# TSAL_Dummy.net
KiCad netlist of a schematic drawn in Altium Designer
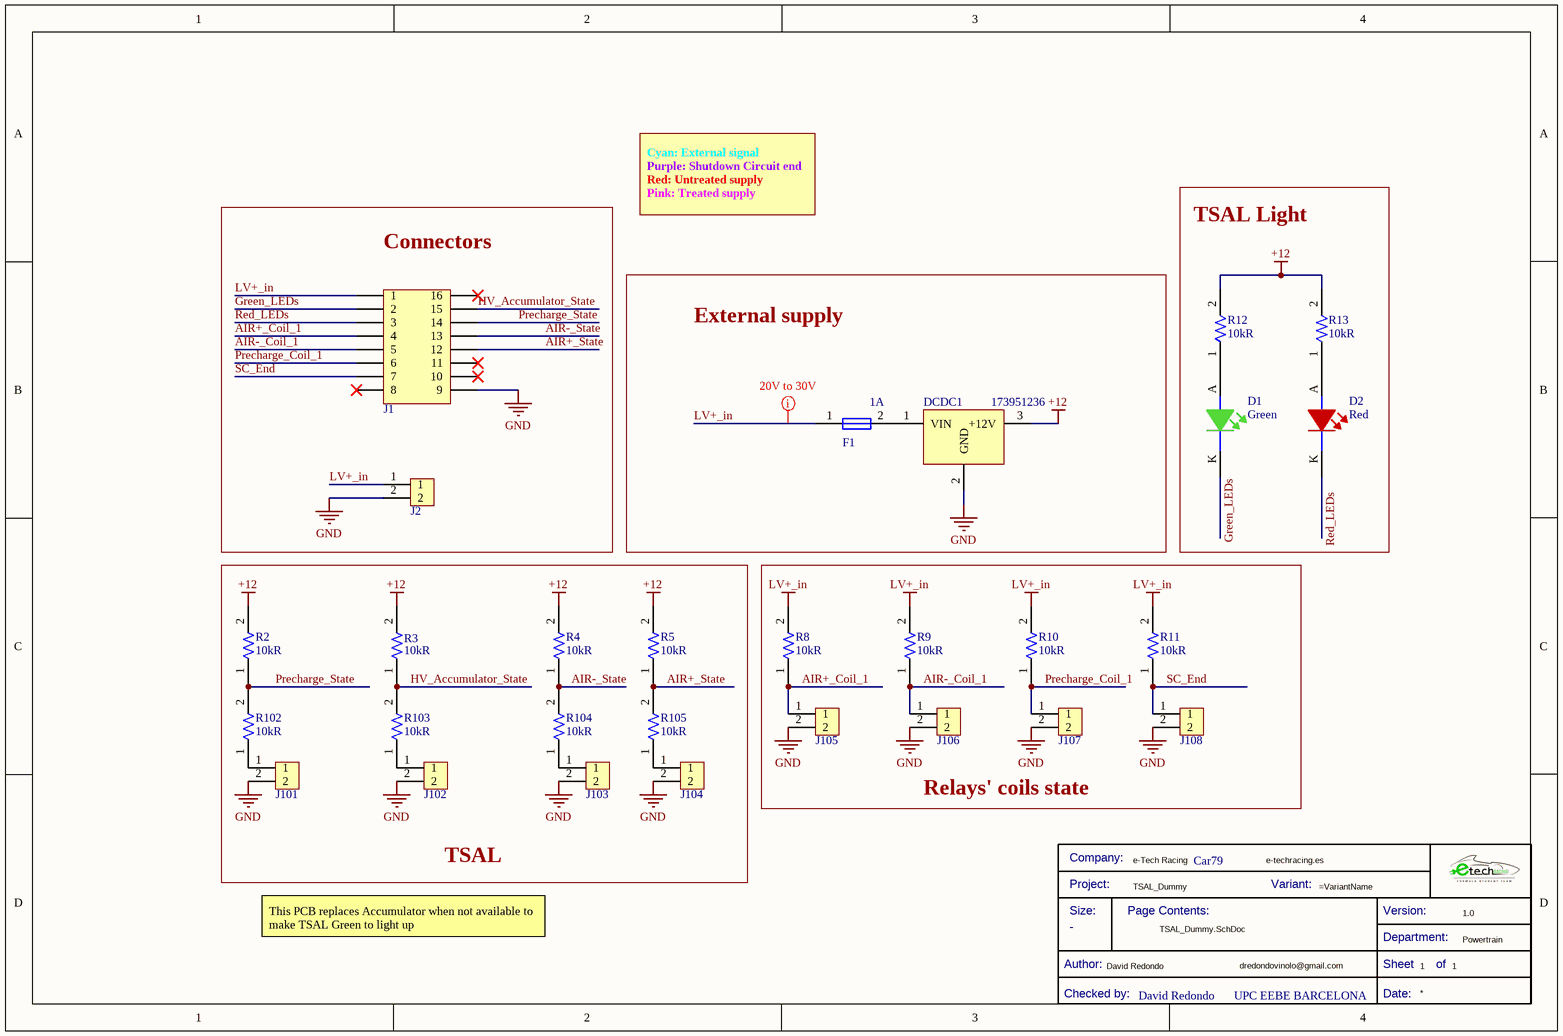
[diagram p0: TSAL_Dummy.SchDoc]

(export (version "E")
  (design (tool "Eeschema 10.0.6"))
  (components
    (comp (ref "*")
      (value "Title Block_template")
      (description "Standard Title Block")
      (fields
        (field (name "SIZE") "-")
        (field (name ".CREATOR") "GP")
        (field (name ".PCBCHECK") "GP")
        (field (name ".SCHCHECK") "GP")
      )
      (libsource (lib "e-Tech_Racing") (part "Title Block_template"))
    )
    (comp (ref "D1")
      (value "150080VS75000")
      (footprint "LED_0805_WE")
      (description "Led, Green, 570 Nm, 2 V, 30 Ma, 40 Mcd Rohs Compliant: Yes")
      (fields (field (name "COLOR") "Green") (field (name ".CREATOR") "DR"))
      (libsource (lib "Semiconductor") (part "LEDVS-0805-40"))
    )
    (comp (ref "D2")
      (value "150080RS75000")
      (footprint "LED_0805_WE")
      (description "0805(H=0.8mm) 红色 高亮 λD=625nm VF=2V IF=30mA PD=72mW")
      (fields (field (name "COLOR") "Red") (field (name ".CREATOR") "DR"))
      (libsource (lib "Semiconductor") (part "LEDRS-0805-150"))
    )
    (comp (ref "DCDC1")
      (value "173951236")
      (footprint "DCDC_Magi3c")
      (description "Fdsm Fixed Step Down Regulator M")
      (libsource (lib "Semiconductor") (part "DCDC-36V/12V-0.5A"))
    )
    (comp (ref "F1")
      (value "0437001.WRA")
      (footprint "Fuse_1206")
      (description "Fuse Chip Fast Acting 1A 63V SMD Solder Pad 1206 Ceramic T/R Automotive")
      (fields
        (field (name "MANUFACTURER") "Littelfuse")
        (field (name "CURRENT RATING") "1A")
        (field (name ".CREATOR") "DO")
      )
      (libsource (lib "Filter components") (part "Fuse_1A_63V_1206"))
    )
    (comp (ref "J1")
      (value "1053101116")
      (footprint "J_NanoFit_2x8_V")
      (fields (field (name ".CREATOR") "AC"))
      (libsource (lib "Electromechanical") (part "J_NanoFit_2x8_V"))
    )
    (comp (ref "J2")
      (value "436500215")
      (footprint "J_MicroFit_2x1")
      (description "Header 1 Row Vertical Polarizing Peg 2 Pin SMT/Glow Wire Compatible Tin Plate")
      (libsource (lib "Electromechanical") (part "J_MicroFit_2x1"))
    )
    (comp (ref "J101")
      (value "61300211121")
      (footprint "J_Pinheader_1x2")
      (description "CONN HEADER 2 POS 2.54")
      (fields (field (name "MANUFACTURER") "Molex") (field (name ".CREATOR") "GP"))
      (libsource (lib "Electromechanical") (part "J_Jumper"))
    )
    (comp (ref "J102")
      (value "61300211121")
      (footprint "J_Pinheader_1x2")
      (description "CONN HEADER 2 POS 2.54")
      (fields (field (name "MANUFACTURER") "Molex") (field (name ".CREATOR") "GP"))
      (libsource (lib "Electromechanical") (part "J_Jumper"))
    )
    (comp (ref "J103")
      (value "61300211121")
      (footprint "J_Pinheader_1x2")
      (description "CONN HEADER 2 POS 2.54")
      (fields (field (name "MANUFACTURER") "Molex") (field (name ".CREATOR") "GP"))
      (libsource (lib "Electromechanical") (part "J_Jumper"))
    )
    (comp (ref "J104")
      (value "61300211121")
      (footprint "J_Pinheader_1x2")
      (description "CONN HEADER 2 POS 2.54")
      (fields (field (name "MANUFACTURER") "Molex") (field (name ".CREATOR") "GP"))
      (libsource (lib "Electromechanical") (part "J_Jumper"))
    )
    (comp (ref "J105")
      (value "61300211121")
      (footprint "J_Pinheader_1x2")
      (description "CONN HEADER 2 POS 2.54")
      (fields (field (name "MANUFACTURER") "Molex") (field (name ".CREATOR") "GP"))
      (libsource (lib "Electromechanical") (part "J_Jumper"))
    )
    (comp (ref "J106")
      (value "61300211121")
      (footprint "J_Pinheader_1x2")
      (description "CONN HEADER 2 POS 2.54")
      (fields (field (name "MANUFACTURER") "Molex") (field (name ".CREATOR") "GP"))
      (libsource (lib "Electromechanical") (part "J_Jumper"))
    )
    (comp (ref "J107")
      (value "61300211121")
      (footprint "J_Pinheader_1x2")
      (description "CONN HEADER 2 POS 2.54")
      (fields (field (name "MANUFACTURER") "Molex") (field (name ".CREATOR") "GP"))
      (libsource (lib "Electromechanical") (part "J_Jumper"))
    )
    (comp (ref "J108")
      (value "61300211121")
      (footprint "J_Pinheader_1x2")
      (description "CONN HEADER 2 POS 2.54")
      (fields (field (name "MANUFACTURER") "Molex") (field (name ".CREATOR") "GP"))
      (libsource (lib "Electromechanical") (part "J_Jumper"))
    )
    (comp (ref "R2")
      (value "CR0805-JW-103ELF")
      (footprint "R0805FTK")
      (fields
        (field (name "TOLERANCE") "5%")
        (field (name "RESISTANCE") "10kR")
        (field (name ".CREATOR") "DR")
      )
      (libsource (lib "Passives") (part "R10k-0805FTK"))
    )
    (comp (ref "R3")
      (value "CR0805-JW-103ELF")
      (footprint "R0805FTK")
      (fields
        (field (name "TOLERANCE") "5%")
        (field (name "RESISTANCE") "10kR")
        (field (name ".CREATOR") "DR")
      )
      (libsource (lib "Passives") (part "R10k-0805FTK"))
    )
    (comp (ref "R4")
      (value "CR0805-JW-103ELF")
      (footprint "R0805FTK")
      (fields
        (field (name "TOLERANCE") "5%")
        (field (name "RESISTANCE") "10kR")
        (field (name ".CREATOR") "DR")
      )
      (libsource (lib "Passives") (part "R10k-0805FTK"))
    )
    (comp (ref "R5")
      (value "CR0805-JW-103ELF")
      (footprint "R0805FTK")
      (fields
        (field (name "TOLERANCE") "5%")
        (field (name "RESISTANCE") "10kR")
        (field (name ".CREATOR") "DR")
      )
      (libsource (lib "Passives") (part "R10k-0805FTK"))
    )
    (comp (ref "R8")
      (value "CR0805-JW-103ELF")
      (footprint "R0805FTK")
      (fields
        (field (name "TOLERANCE") "5%")
        (field (name "RESISTANCE") "10kR")
        (field (name ".CREATOR") "DR")
      )
      (libsource (lib "Passives") (part "R10k-0805FTK"))
    )
    (comp (ref "R9")
      (value "CR0805-JW-103ELF")
      (footprint "R0805FTK")
      (fields
        (field (name "TOLERANCE") "5%")
        (field (name "RESISTANCE") "10kR")
        (field (name ".CREATOR") "DR")
      )
      (libsource (lib "Passives") (part "R10k-0805FTK"))
    )
    (comp (ref "R10")
      (value "CR0805-JW-103ELF")
      (footprint "R0805FTK")
      (fields
        (field (name "TOLERANCE") "5%")
        (field (name "RESISTANCE") "10kR")
        (field (name ".CREATOR") "DR")
      )
      (libsource (lib "Passives") (part "R10k-0805FTK"))
    )
    (comp (ref "R11")
      (value "CR0805-JW-103ELF")
      (footprint "R0805FTK")
      (fields
        (field (name "TOLERANCE") "5%")
        (field (name "RESISTANCE") "10kR")
        (field (name ".CREATOR") "DR")
      )
      (libsource (lib "Passives") (part "R10k-0805FTK"))
    )
    (comp (ref "R12")
      (value "CR0805-JW-103ELF")
      (footprint "R0805FTK")
      (fields
        (field (name "TOLERANCE") "5%")
        (field (name "RESISTANCE") "10kR")
        (field (name ".CREATOR") "DR")
      )
      (libsource (lib "Passives") (part "R10k-0805FTK"))
    )
    (comp (ref "R13")
      (value "CR0805-JW-103ELF")
      (footprint "R0805FTK")
      (fields
        (field (name "TOLERANCE") "5%")
        (field (name "RESISTANCE") "10kR")
        (field (name ".CREATOR") "DR")
      )
      (libsource (lib "Passives") (part "R10k-0805FTK"))
    )
    (comp (ref "R102")
      (value "CR0805-JW-103ELF")
      (footprint "R0805FTK")
      (fields
        (field (name "TOLERANCE") "5%")
        (field (name "RESISTANCE") "10kR")
        (field (name ".CREATOR") "DR")
      )
      (libsource (lib "Passives") (part "R10k-0805FTK"))
    )
    (comp (ref "R103")
      (value "CR0805-JW-103ELF")
      (footprint "R0805FTK")
      (fields
        (field (name "TOLERANCE") "5%")
        (field (name "RESISTANCE") "10kR")
        (field (name ".CREATOR") "DR")
      )
      (libsource (lib "Passives") (part "R10k-0805FTK"))
    )
    (comp (ref "R104")
      (value "CR0805-JW-103ELF")
      (footprint "R0805FTK")
      (fields
        (field (name "TOLERANCE") "5%")
        (field (name "RESISTANCE") "10kR")
        (field (name ".CREATOR") "DR")
      )
      (libsource (lib "Passives") (part "R10k-0805FTK"))
    )
    (comp (ref "R105")
      (value "CR0805-JW-103ELF")
      (footprint "R0805FTK")
      (fields
        (field (name "TOLERANCE") "5%")
        (field (name "RESISTANCE") "10kR")
        (field (name ".CREATOR") "DR")
      )
      (libsource (lib "Passives") (part "R10k-0805FTK"))
    )
  )
  (nets
    (net (code "1") (name "+12") (class "Default")
      (node (ref "DCDC1") (pin "3") (pinfunction "+12V_3") (pintype "passive"))
      (node (ref "R12") (pin "2") (pinfunction "2_2") (pintype "passive"))
      (node (ref "R13") (pin "2") (pinfunction "2_2") (pintype "passive"))
      (node (ref "R2") (pin "2") (pinfunction "2_2") (pintype "passive"))
      (node (ref "R3") (pin "2") (pinfunction "2_2") (pintype "passive"))
      (node (ref "R4") (pin "2") (pinfunction "2_2") (pintype "passive"))
      (node (ref "R5") (pin "2") (pinfunction "2_2") (pintype "passive"))
    )
    (net (code "2") (name "/AIR+_Coil_1") (class "Default")
      (node (ref "J1") (pin "4") (pinfunction "4_4") (pintype "passive"))
      (node (ref "J105") (pin "1") (pinfunction "1_1") (pintype "passive"))
      (node (ref "R8") (pin "1") (pinfunction "1_1") (pintype "passive"))
    )
    (net (code "3") (name "/AIR+_State") (class "Default")
      (node (ref "J1") (pin "12") (pinfunction "12_12") (pintype "passive"))
      (node (ref "R105") (pin "2") (pinfunction "2_2") (pintype "passive"))
      (node (ref "R5") (pin "1") (pinfunction "1_1") (pintype "passive"))
    )
    (net (code "4") (name "/AIR-_Coil_1") (class "Default")
      (node (ref "J1") (pin "5") (pinfunction "5_5") (pintype "passive"))
      (node (ref "J106") (pin "1") (pinfunction "1_1") (pintype "passive"))
      (node (ref "R9") (pin "1") (pinfunction "1_1") (pintype "passive"))
    )
    (net (code "5") (name "/AIR-_State") (class "Default")
      (node (ref "J1") (pin "13") (pinfunction "13_13") (pintype "passive"))
      (node (ref "R104") (pin "2") (pinfunction "2_2") (pintype "passive"))
      (node (ref "R4") (pin "1") (pinfunction "1_1") (pintype "passive"))
    )
    (net (code "6") (name "/Green_LEDs") (class "Default")
      (node (ref "D1") (pin "K") (pinfunction "K_K") (pintype "passive"))
      (node (ref "J1") (pin "2") (pinfunction "2_2") (pintype "passive"))
    )
    (net (code "7") (name "/HV_Accumulator_State") (class "Default")
      (node (ref "J1") (pin "15") (pinfunction "15_15") (pintype "passive"))
      (node (ref "R103") (pin "2") (pinfunction "2_2") (pintype "passive"))
      (node (ref "R3") (pin "1") (pinfunction "1_1") (pintype "passive"))
    )
    (net (code "8") (name "/Precharge_Coil_1") (class "Default")
      (node (ref "J1") (pin "6") (pinfunction "6_6") (pintype "passive"))
      (node (ref "J107") (pin "1") (pinfunction "1_1") (pintype "passive"))
      (node (ref "R10") (pin "1") (pinfunction "1_1") (pintype "passive"))
    )
    (net (code "9") (name "/Precharge_State") (class "Default")
      (node (ref "J1") (pin "14") (pinfunction "14_14") (pintype "passive"))
      (node (ref "R102") (pin "2") (pinfunction "2_2") (pintype "passive"))
      (node (ref "R2") (pin "1") (pinfunction "1_1") (pintype "passive"))
    )
    (net (code "10") (name "/Red_LEDs") (class "Default")
      (node (ref "D2") (pin "K") (pinfunction "K_K") (pintype "passive"))
      (node (ref "J1") (pin "3") (pinfunction "3_3") (pintype "passive"))
    )
    (net (code "11") (name "/SC_End") (class "Default")
      (node (ref "J1") (pin "7") (pinfunction "7_7") (pintype "passive"))
      (node (ref "J108") (pin "1") (pinfunction "1_1") (pintype "passive"))
      (node (ref "R11") (pin "1") (pinfunction "1_1") (pintype "passive"))
    )
    (net (code "12") (name "GND") (class "Default")
      (node (ref "DCDC1") (pin "2") (pinfunction "GND_2") (pintype "passive"))
      (node (ref "J1") (pin "9") (pinfunction "9_9") (pintype "passive"))
      (node (ref "J101") (pin "2") (pinfunction "2_2") (pintype "passive"))
      (node (ref "J102") (pin "2") (pinfunction "2_2") (pintype "passive"))
      (node (ref "J103") (pin "2") (pinfunction "2_2") (pintype "passive"))
      (node (ref "J104") (pin "2") (pinfunction "2_2") (pintype "passive"))
      (node (ref "J105") (pin "2") (pinfunction "2_2") (pintype "passive"))
      (node (ref "J106") (pin "2") (pinfunction "2_2") (pintype "passive"))
      (node (ref "J107") (pin "2") (pinfunction "2_2") (pintype "passive"))
      (node (ref "J108") (pin "2") (pinfunction "2_2") (pintype "passive"))
      (node (ref "J2") (pin "2") (pinfunction "2_2") (pintype "passive"))
    )
    (net (code "13") (name "LV+_in") (class "Default")
      (node (ref "F1") (pin "1") (pinfunction "1_1") (pintype "passive"))
      (node (ref "J1") (pin "1") (pinfunction "1_1") (pintype "passive"))
      (node (ref "J2") (pin "1") (pinfunction "1_1") (pintype "passive"))
      (node (ref "R10") (pin "2") (pinfunction "2_2") (pintype "passive"))
      (node (ref "R11") (pin "2") (pinfunction "2_2") (pintype "passive"))
      (node (ref "R8") (pin "2") (pinfunction "2_2") (pintype "passive"))
      (node (ref "R9") (pin "2") (pinfunction "2_2") (pintype "passive"))
    )
    (net (code "14") (name "Net-(D1-PadA)") (class "Default")
      (node (ref "D1") (pin "A") (pinfunction "A_A") (pintype "passive"))
      (node (ref "R12") (pin "1") (pinfunction "1_1") (pintype "passive"))
    )
    (net (code "15") (name "Net-(D2-PadA)") (class "Default")
      (node (ref "D2") (pin "A") (pinfunction "A_A") (pintype "passive"))
      (node (ref "R13") (pin "1") (pinfunction "1_1") (pintype "passive"))
    )
    (net (code "16") (name "Net-(DCDC1-VIN)") (class "Default")
      (node (ref "DCDC1") (pin "1") (pinfunction "VIN_1") (pintype "passive"))
      (node (ref "F1") (pin "2") (pinfunction "2_2") (pintype "passive"))
    )
    (net (code "17") (name "Net-(J101-Pad1)") (class "Default")
      (node (ref "J101") (pin "1") (pinfunction "1_1") (pintype "passive"))
      (node (ref "R102") (pin "1") (pinfunction "1_1") (pintype "passive"))
    )
    (net (code "18") (name "Net-(J102-Pad1)") (class "Default")
      (node (ref "J102") (pin "1") (pinfunction "1_1") (pintype "passive"))
      (node (ref "R103") (pin "1") (pinfunction "1_1") (pintype "passive"))
    )
    (net (code "19") (name "Net-(J103-Pad1)") (class "Default")
      (node (ref "J103") (pin "1") (pinfunction "1_1") (pintype "passive"))
      (node (ref "R104") (pin "1") (pinfunction "1_1") (pintype "passive"))
    )
    (net (code "20") (name "Net-(J104-Pad1)") (class "Default")
      (node (ref "J104") (pin "1") (pinfunction "1_1") (pintype "passive"))
      (node (ref "R105") (pin "1") (pinfunction "1_1") (pintype "passive"))
    )
    (net (code "21") (name "unconnected-(J1-Pad8)") (class "Default")
      (node (ref "J1") (pin "8") (pinfunction "8_8") (pintype "passive+no_connect"))
    )
    (net (code "22") (name "unconnected-(J1-Pad10)") (class "Default")
      (node (ref "J1") (pin "10") (pinfunction "10_10") (pintype "passive+no_connect"))
    )
    (net (code "23") (name "unconnected-(J1-Pad11)") (class "Default")
      (node (ref "J1") (pin "11") (pinfunction "11_11") (pintype "passive+no_connect"))
    )
    (net (code "24") (name "unconnected-(J1-Pad16)") (class "Default")
      (node (ref "J1") (pin "16") (pinfunction "16_16") (pintype "passive+no_connect"))
    )
  )
)
